# Microcontroller.net
KiCad netlist of a schematic drawn in Altium Designer
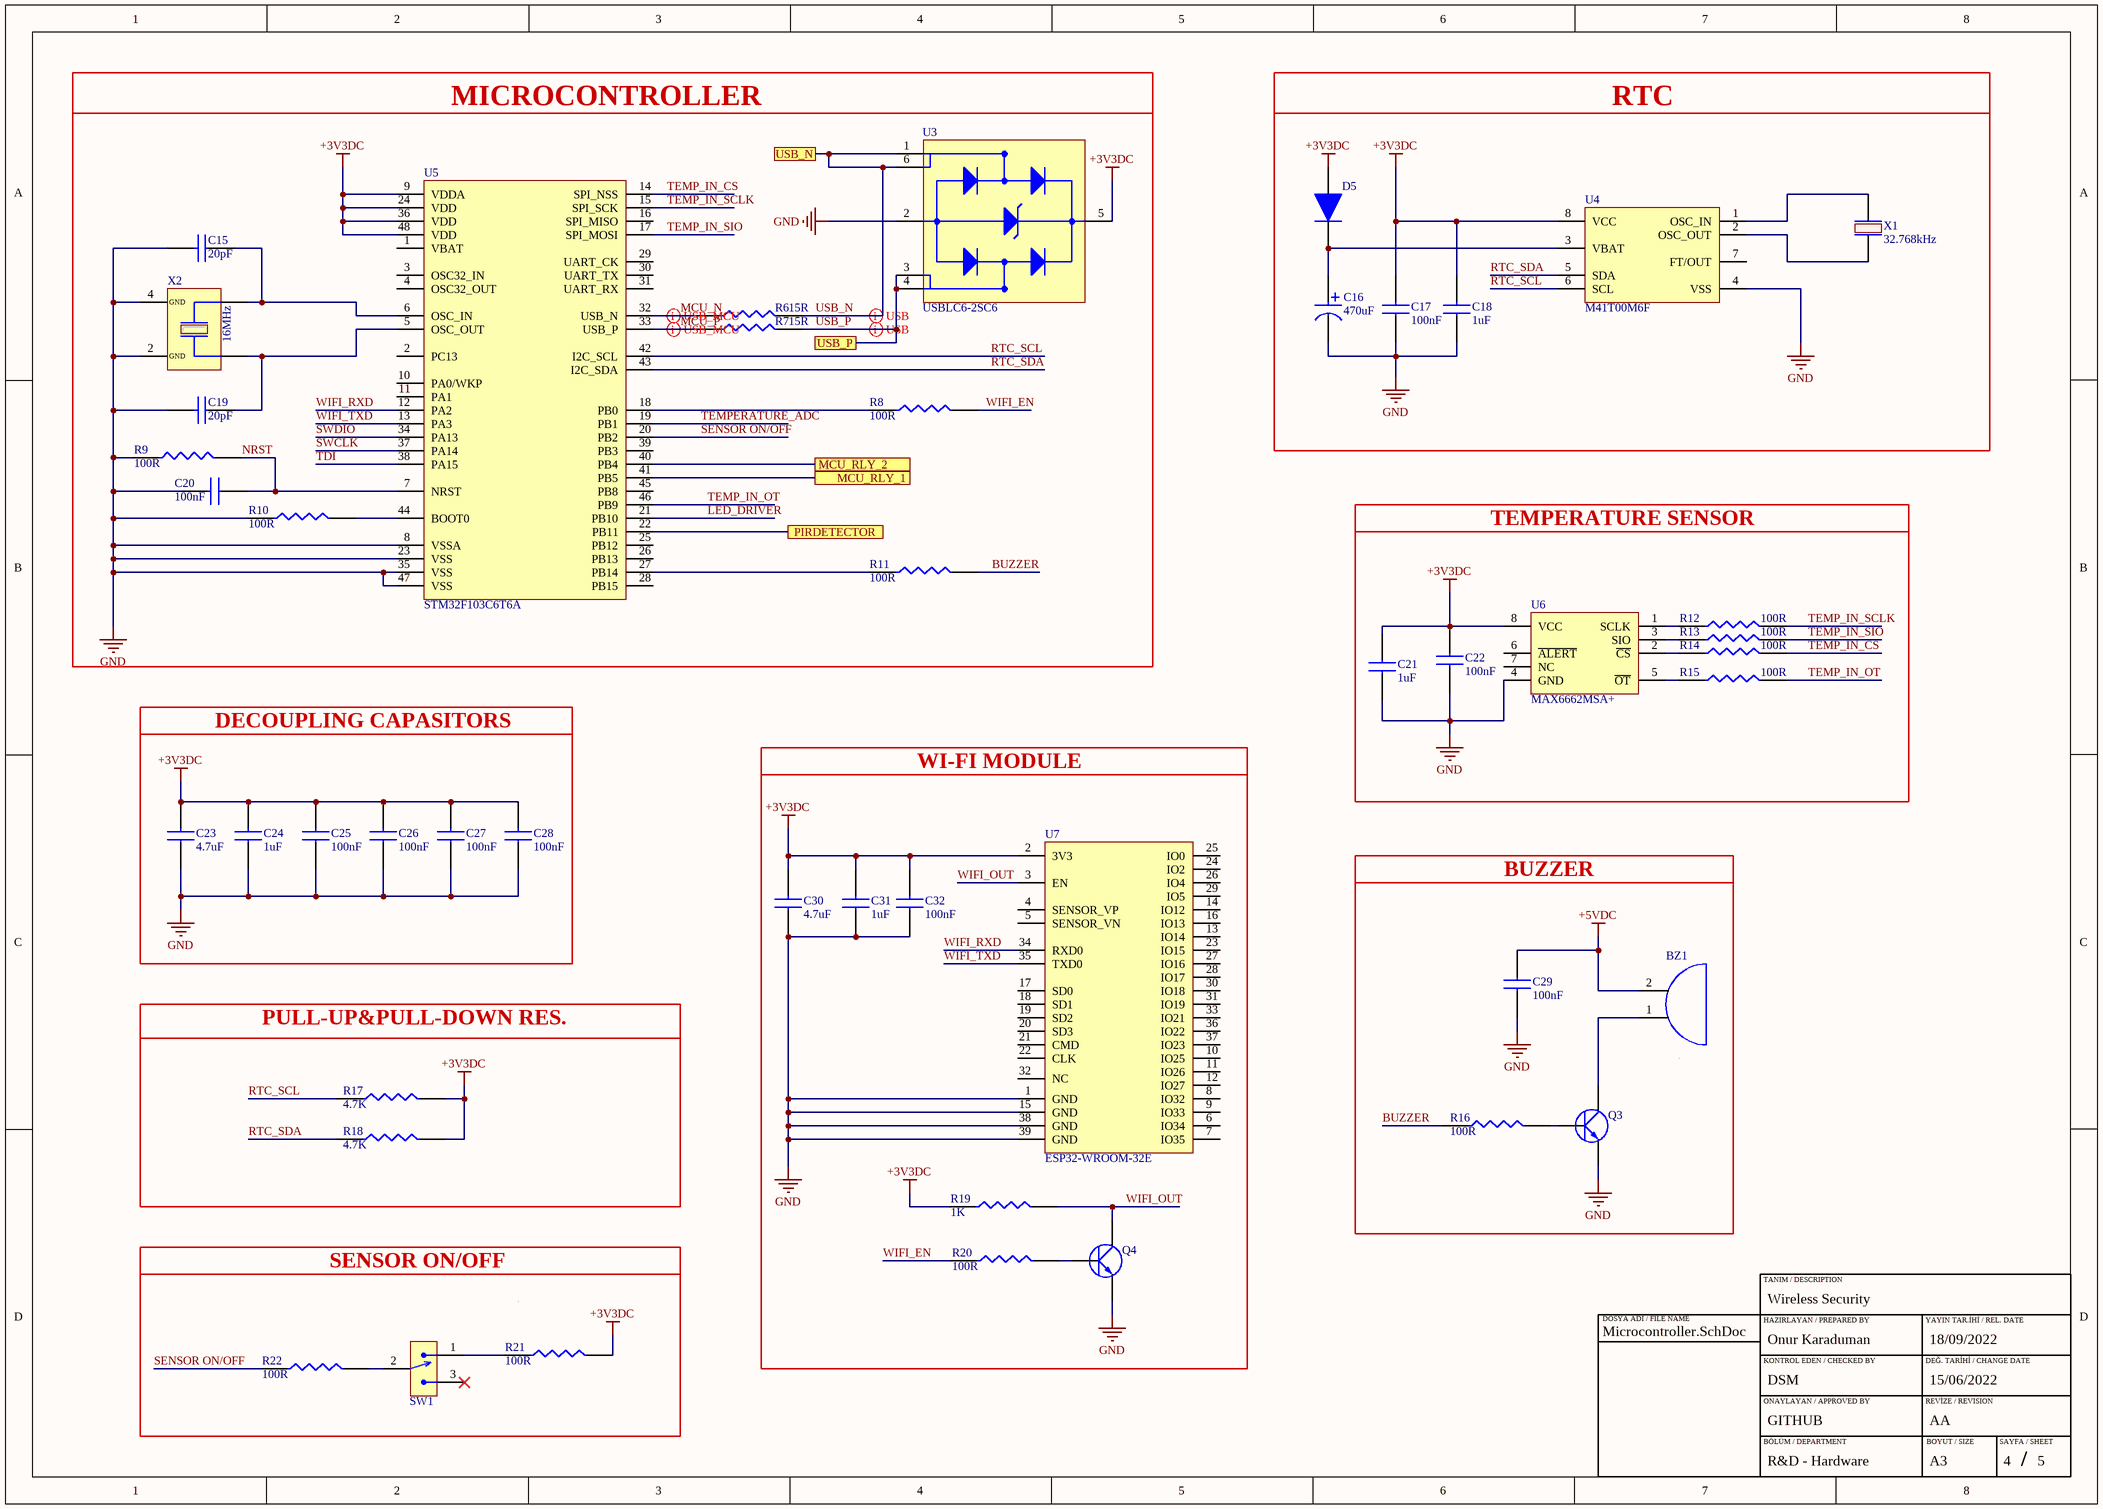
[diagram p0: Microcontroller.SchDoc]

(export (version "E")
  (design (tool "Eeschema 10.0.6"))
  (components
    (comp (ref "BZ1")
      (value "CMI-96051C-0580T")
      (footprint "CMI-9605IC-0580T")
      (description "Audio Buzzer Magnetic 3VDC 7VDC 30mA 5VDC 85dB 2600Hz to 2800Hz Through Hole Pin Box")
      (fields
        (field (name "MANUFACTURER") "CUI Devices")
        (field (name "MANUFACTURER PART NUMBER") "CMI-9605IC-0580T")
        (field (name "DESIGNED BY") "Onur Karaduman")
      )
      (libsource (lib "Ders1Lib") (part "CMI-96051C-0580T"))
    )
    (comp (ref "C15")
      (value "CL10C200JB8NNNC")
      (footprint "CAP_0603")
      (description "CAP CER 20pF %5 0603 SMD")
      (fields
        (field (name "MANUFACTURER") "Samsung")
        (field (name "TOLERANCE") "5%")
        (field (name "CAPACITANCE") "20pF")
        (field (name "DESIGNED BY") "BERK")
      )
      (libsource (lib "UDEMY_Library") (part "CAP CER 20pF 0603"))
    )
    (comp (ref "C16")
      (value "ESH477M050AH4AA")
      (footprint "ESH477M050AH4AA")
      (description "Cap, 470UF, 50V, Alu Elec, Radial")
      (fields
        (field (name "MANUFACTURER") "KEMET")
        (field (name "TOLERANCE") "20%")
        (field (name "CAPACITANCE") "470uF")
        (field (name "DESIGNED BY") "Onur Karaduman")
      )
      (libsource (lib "Ders1Lib") (part "ESH477M050AH4AA"))
    )
    (comp (ref "C17")
      (value "CL21B104KBCNNNC")
      (footprint "CAP_0805")
      (description "CAP CER 0.1UF 50V X7R 0805")
      (fields
        (field (name "MANUFACTURER") "Samsung")
        (field (name "TOLERANCE") "10%")
        (field (name "CAPACITANCE") "100nF")
        (field (name "DESIGNED BY") "Onur Karaduman")
      )
      (libsource (lib "Ders1Lib") (part "CAP CER 100nF 0805"))
    )
    (comp (ref "C18")
      (value "CL21B105KBFNNNE")
      (footprint "CAP_0805")
      (description "CAP CER 1UF 50V X7R 0805")
      (fields
        (field (name "MANUFACTURER") "Samsung")
        (field (name "TOLERANCE") "10%")
        (field (name "CAPACITANCE") "1uF")
        (field (name "DESIGNED BY") "Onur Karaduman")
      )
      (libsource (lib "Ders1Lib") (part "CAP CER 1uF 0805"))
    )
    (comp (ref "C19")
      (value "CL10C200JB8NNNC")
      (footprint "CAP_0603")
      (description "CAP CER 20pF %5 0603 SMD")
      (fields
        (field (name "MANUFACTURER") "Samsung")
        (field (name "TOLERANCE") "5%")
        (field (name "CAPACITANCE") "20pF")
        (field (name "DESIGNED BY") "BERK")
      )
      (libsource (lib "UDEMY_Library") (part "CAP CER 20pF 0603"))
    )
    (comp (ref "C20")
      (value "C0603C104K4RACTU")
      (footprint "CAP_0603")
      (description "Cap Cer 0.1uF 16V X7R 10% SMD 0603 125°C Paper T/R")
      (fields
        (field (name "MANUFACTURER") "KEMET")
        (field (name "TOLERANCE") "10%")
        (field (name "CAPACITANCE") "100nF")
        (field (name "DESIGNED BY") "Onur Karaduman")
      )
      (libsource (lib "Ders1Lib") (part "CAP CER 100nF 0603"))
    )
    (comp (ref "C21")
      (value "CL21B105KBFNNNE")
      (footprint "CAP_0805")
      (description "CAP CER 1UF 50V X7R 0805")
      (fields
        (field (name "MANUFACTURER") "Samsung")
        (field (name "TOLERANCE") "10%")
        (field (name "CAPACITANCE") "1uF")
        (field (name "DESIGNED BY") "Onur Karaduman")
      )
      (libsource (lib "Ders1Lib") (part "CAP CER 1uF 0805"))
    )
    (comp (ref "C22")
      (value "CL21B104KBCNNNC")
      (footprint "CAP_0805")
      (description "CAP CER 0.1UF 50V X7R 0805")
      (fields
        (field (name "MANUFACTURER") "Samsung")
        (field (name "TOLERANCE") "10%")
        (field (name "CAPACITANCE") "100nF")
        (field (name "DESIGNED BY") "Onur Karaduman")
      )
      (libsource (lib "Ders1Lib") (part "CAP CER 100nF 0805"))
    )
    (comp (ref "C23")
      (value "CL21A475KAQNNNE")
      (footprint "CAP_0805")
      (description "CAP CER 4.7UF 25V X5R 0805")
      (fields
        (field (name "MANUFACTURER") "Samsung")
        (field (name "TOLERANCE") "10%")
        (field (name "CAPACITANCE") "4.7uF")
        (field (name "DESIGNED BY") "Onur Karaduman")
      )
      (libsource (lib "Ders1Lib") (part "CAP CER 4.7uF 0805"))
    )
    (comp (ref "C24")
      (value "CL21B105KBFNNNE")
      (footprint "CAP_0805")
      (description "CAP CER 1UF 50V X7R 0805")
      (fields
        (field (name "MANUFACTURER") "Samsung")
        (field (name "TOLERANCE") "10%")
        (field (name "CAPACITANCE") "1uF")
        (field (name "DESIGNED BY") "Onur Karaduman")
      )
      (libsource (lib "Ders1Lib") (part "CAP CER 1uF 0805"))
    )
    (comp (ref "C25")
      (value "C0603C104K4RACTU")
      (footprint "CAP_0603")
      (description "Cap Cer 0.1uF 16V X7R 10% SMD 0603 125°C Paper T/R")
      (fields
        (field (name "MANUFACTURER") "KEMET")
        (field (name "TOLERANCE") "10%")
        (field (name "CAPACITANCE") "100nF")
        (field (name "DESIGNED BY") "Onur Karaduman")
      )
      (libsource (lib "Ders1Lib") (part "CAP CER 100nF 0603"))
    )
    (comp (ref "C26")
      (value "C0603C104K4RACTU")
      (footprint "CAP_0603")
      (description "Cap Cer 0.1uF 16V X7R 10% SMD 0603 125°C Paper T/R")
      (fields
        (field (name "MANUFACTURER") "KEMET")
        (field (name "TOLERANCE") "10%")
        (field (name "CAPACITANCE") "100nF")
        (field (name "DESIGNED BY") "Onur Karaduman")
      )
      (libsource (lib "Ders1Lib") (part "CAP CER 100nF 0603"))
    )
    (comp (ref "C27")
      (value "C0603C104K4RACTU")
      (footprint "CAP_0603")
      (description "Cap Cer 0.1uF 16V X7R 10% SMD 0603 125°C Paper T/R")
      (fields
        (field (name "MANUFACTURER") "KEMET")
        (field (name "TOLERANCE") "10%")
        (field (name "CAPACITANCE") "100nF")
        (field (name "DESIGNED BY") "Onur Karaduman")
      )
      (libsource (lib "Ders1Lib") (part "CAP CER 100nF 0603"))
    )
    (comp (ref "C28")
      (value "C0603C104K4RACTU")
      (footprint "CAP_0603")
      (description "Cap Cer 0.1uF 16V X7R 10% SMD 0603 125°C Paper T/R")
      (fields
        (field (name "MANUFACTURER") "KEMET")
        (field (name "TOLERANCE") "10%")
        (field (name "CAPACITANCE") "100nF")
        (field (name "DESIGNED BY") "Onur Karaduman")
      )
      (libsource (lib "Ders1Lib") (part "CAP CER 100nF 0603"))
    )
    (comp (ref "C29")
      (value "CL21B104KBCNNNC")
      (footprint "CAP_0805")
      (description "CAP CER 0.1UF 50V X7R 0805")
      (fields
        (field (name "MANUFACTURER") "Samsung")
        (field (name "TOLERANCE") "10%")
        (field (name "CAPACITANCE") "100nF")
        (field (name "DESIGNED BY") "Onur Karaduman")
      )
      (libsource (lib "Ders1Lib") (part "CAP CER 100nF 0805"))
    )
    (comp (ref "C30")
      (value "CL21A475KAQNNNE")
      (footprint "CAP_0805")
      (description "CAP CER 4.7UF 25V X5R 0805")
      (fields
        (field (name "MANUFACTURER") "Samsung")
        (field (name "TOLERANCE") "10%")
        (field (name "CAPACITANCE") "4.7uF")
        (field (name "DESIGNED BY") "Onur Karaduman")
      )
      (libsource (lib "Ders1Lib") (part "CAP CER 4.7uF 0805"))
    )
    (comp (ref "C31")
      (value "CL21B105KBFNNNE")
      (footprint "CAP_0805")
      (description "CAP CER 1UF 50V X7R 0805")
      (fields
        (field (name "MANUFACTURER") "Samsung")
        (field (name "TOLERANCE") "10%")
        (field (name "CAPACITANCE") "1uF")
        (field (name "DESIGNED BY") "Onur Karaduman")
      )
      (libsource (lib "Ders1Lib") (part "CAP CER 1uF 0805"))
    )
    (comp (ref "C32")
      (value "CL21B104KBCNNNC")
      (footprint "CAP_0805")
      (description "CAP CER 0.1UF 50V X7R 0805")
      (fields
        (field (name "MANUFACTURER") "Samsung")
        (field (name "TOLERANCE") "10%")
        (field (name "CAPACITANCE") "100nF")
        (field (name "DESIGNED BY") "Onur Karaduman")
      )
      (libsource (lib "Ders1Lib") (part "CAP CER 100nF 0805"))
    )
    (comp (ref "D5")
      (value "1N4148WS")
      (footprint "SOD32-F")
      (description "VR=75V IF=150mA Trr=4ns P=200mW")
      (fields
        (field (name "MANUFACTURER") "ON Semiconductor / Fairchild")
        (field (name "DESIGNED BY") "Onur Karaduman")
      )
      (libsource (lib "Ders1Lib") (part "1N4148WS"))
    )
    (comp (ref "Q3")
      (value "MMBT3904-7-F")
      (footprint "SOT23-F")
      (description "NPN Ic=200mA Vceo=40V hfe=100~300 fT=310MHz P=300mW SOT-23")
      (fields (field (name "MANUFACTURER") "Diodes Zetex") (field (name "DESIGNED BY") "Onur Karaduman"))
      (libsource (lib "Ders1Lib") (part "MMBT3904-7-F"))
    )
    (comp (ref "Q4")
      (value "MMBT3904-7-F")
      (footprint "SOT23-F")
      (description "NPN Ic=200mA Vceo=40V hfe=100~300 fT=310MHz P=300mW SOT-23")
      (fields (field (name "MANUFACTURER") "Diodes Zetex") (field (name "DESIGNED BY") "Onur Karaduman"))
      (libsource (lib "Ders1Lib") (part "MMBT3904-7-F"))
    )
    (comp (ref "R6")
      (value "RC0603JR-0715RL")
      (footprint "RES_0603")
      (description "Res Thick Film 0603 15 Ohm 5% 0.1W(1/10W) ±100ppm/C Pad SMD T/R")
      (fields
        (field (name "MANUFACTURER") "Yageo")
        (field (name "TOLERANCE") "5%")
        (field (name "RESISTANCE") "15R")
        (field (name "DESIGNED BY") "Onur Karaduman")
      )
      (libsource (lib "Ders1Lib") (part "RES 15 OHM 0603"))
    )
    (comp (ref "R7")
      (value "RC0603JR-0715RL")
      (footprint "RES_0603")
      (description "Res Thick Film 0603 15 Ohm 5% 0.1W(1/10W) ±100ppm/C Pad SMD T/R")
      (fields
        (field (name "MANUFACTURER") "Yageo")
        (field (name "TOLERANCE") "5%")
        (field (name "RESISTANCE") "15R")
        (field (name "DESIGNED BY") "Onur Karaduman")
      )
      (libsource (lib "Ders1Lib") (part "RES 15 OHM 0603"))
    )
    (comp (ref "R8")
      (value "RC0603JR-07100RL")
      (footprint "RES_0603")
      (description "Res Thick Film 0603 100 Ohm 5% 1/10W ±100ppm/°C Molded SMD SMD Paper T/R")
      (fields
        (field (name "MANUFACTURER") "Yageo")
        (field (name "TOLERANCE") "5%")
        (field (name "RESISTANCE") "100R")
        (field (name "DESIGNED BY") "Onur Karaduman")
      )
      (libsource (lib "Ders1Lib") (part "RES 100 OHM 0603"))
    )
    (comp (ref "R9")
      (value "RC0603JR-07100RL")
      (footprint "RES_0603")
      (description "Res Thick Film 0603 100 Ohm 5% 1/10W ±100ppm/°C Molded SMD SMD Paper T/R")
      (fields
        (field (name "MANUFACTURER") "Yageo")
        (field (name "TOLERANCE") "5%")
        (field (name "RESISTANCE") "100R")
        (field (name "DESIGNED BY") "Onur Karaduman")
      )
      (libsource (lib "Ders1Lib") (part "RES 100 OHM 0603"))
    )
    (comp (ref "R10")
      (value "RC0603JR-07100RL")
      (footprint "RES_0603")
      (description "Res Thick Film 0603 100 Ohm 5% 1/10W ±100ppm/°C Molded SMD SMD Paper T/R")
      (fields
        (field (name "MANUFACTURER") "Yageo")
        (field (name "TOLERANCE") "5%")
        (field (name "RESISTANCE") "100R")
        (field (name "DESIGNED BY") "Onur Karaduman")
      )
      (libsource (lib "Ders1Lib") (part "RES 100 OHM 0603"))
    )
    (comp (ref "R11")
      (value "RC0603JR-07100RL")
      (footprint "RES_0603")
      (description "Res Thick Film 0603 100 Ohm 5% 1/10W ±100ppm/°C Molded SMD SMD Paper T/R")
      (fields
        (field (name "MANUFACTURER") "Yageo")
        (field (name "TOLERANCE") "5%")
        (field (name "RESISTANCE") "100R")
        (field (name "DESIGNED BY") "Onur Karaduman")
      )
      (libsource (lib "Ders1Lib") (part "RES 100 OHM 0603"))
    )
    (comp (ref "R12")
      (value "RC0603JR-07100RL")
      (footprint "RES_0603")
      (description "Res Thick Film 0603 100 Ohm 5% 1/10W ±100ppm/°C Molded SMD SMD Paper T/R")
      (fields
        (field (name "MANUFACTURER") "Yageo")
        (field (name "TOLERANCE") "5%")
        (field (name "RESISTANCE") "100R")
        (field (name "DESIGNED BY") "Onur Karaduman")
      )
      (libsource (lib "Ders1Lib") (part "RES 100 OHM 0603"))
    )
    (comp (ref "R13")
      (value "RC0603JR-07100RL")
      (footprint "RES_0603")
      (description "Res Thick Film 0603 100 Ohm 5% 1/10W ±100ppm/°C Molded SMD SMD Paper T/R")
      (fields
        (field (name "MANUFACTURER") "Yageo")
        (field (name "TOLERANCE") "5%")
        (field (name "RESISTANCE") "100R")
        (field (name "DESIGNED BY") "Onur Karaduman")
      )
      (libsource (lib "Ders1Lib") (part "RES 100 OHM 0603"))
    )
    (comp (ref "R14")
      (value "RC0603JR-07100RL")
      (footprint "RES_0603")
      (description "Res Thick Film 0603 100 Ohm 5% 1/10W ±100ppm/°C Molded SMD SMD Paper T/R")
      (fields
        (field (name "MANUFACTURER") "Yageo")
        (field (name "TOLERANCE") "5%")
        (field (name "RESISTANCE") "100R")
        (field (name "DESIGNED BY") "Onur Karaduman")
      )
      (libsource (lib "Ders1Lib") (part "RES 100 OHM 0603"))
    )
    (comp (ref "R15")
      (value "RC0603JR-07100RL")
      (footprint "RES_0603")
      (description "Res Thick Film 0603 100 Ohm 5% 1/10W ±100ppm/°C Molded SMD SMD Paper T/R")
      (fields
        (field (name "MANUFACTURER") "Yageo")
        (field (name "TOLERANCE") "5%")
        (field (name "RESISTANCE") "100R")
        (field (name "DESIGNED BY") "Onur Karaduman")
      )
      (libsource (lib "Ders1Lib") (part "RES 100 OHM 0603"))
    )
    (comp (ref "R16")
      (value "RC0603JR-07100RL")
      (footprint "RES_0603")
      (description "Res Thick Film 0603 100 Ohm 5% 1/10W ±100ppm/°C Molded SMD SMD Paper T/R")
      (fields
        (field (name "MANUFACTURER") "Yageo")
        (field (name "TOLERANCE") "5%")
        (field (name "RESISTANCE") "100R")
        (field (name "DESIGNED BY") "Onur Karaduman")
      )
      (libsource (lib "Ders1Lib") (part "RES 100 OHM 0603"))
    )
    (comp (ref "R17")
      (value "RC0603JR-074K7L")
      (footprint "RES_0603")
      (description "Res General Purpose Thick Film 0603 4.7k Ohm 5% 1/10W ±100ppm/°C Molded Paper T/R")
      (fields
        (field (name "MANUFACTURER") "Yageo")
        (field (name "TOLERANCE") "5%")
        (field (name "RESISTANCE") "4.7K")
        (field (name "DESIGNED BY") "Onur Karaduman")
      )
      (libsource (lib "Ders1Lib") (part "RES 4K7 OHM 0603"))
    )
    (comp (ref "R18")
      (value "RC0603JR-074K7L")
      (footprint "RES_0603")
      (description "Res General Purpose Thick Film 0603 4.7k Ohm 5% 1/10W ±100ppm/°C Molded Paper T/R")
      (fields
        (field (name "MANUFACTURER") "Yageo")
        (field (name "TOLERANCE") "5%")
        (field (name "RESISTANCE") "4.7K")
        (field (name "DESIGNED BY") "Onur Karaduman")
      )
      (libsource (lib "Ders1Lib") (part "RES 4K7 OHM 0603"))
    )
    (comp (ref "R19")
      (value "RES 1K OHM 0603")
      (footprint "RES_0603")
      (description "Res Thick Film 0603 1K Ohm 1% 0.25W(1/4W) ±100ppm/°C Epoxy Resin Pad SMD Automotive T/R")
      (fields
        (field (name "MANUFACTURER") "Rohm")
        (field (name "MANUFACTURER PART NUMBER") "ESR03EZPF1001")
        (field (name "RESISTANCE") "1K")
        (field (name "DESIGNED BY") "Onur Karaduman")
      )
      (libsource (lib "Ders1Lib") (part "RES 1K OHM 0603"))
    )
    (comp (ref "R20")
      (value "RC0603JR-07100RL")
      (footprint "RES_0603")
      (description "Res Thick Film 0603 100 Ohm 5% 1/10W ±100ppm/°C Molded SMD SMD Paper T/R")
      (fields
        (field (name "MANUFACTURER") "Yageo")
        (field (name "TOLERANCE") "5%")
        (field (name "RESISTANCE") "100R")
        (field (name "DESIGNED BY") "Onur Karaduman")
      )
      (libsource (lib "Ders1Lib") (part "RES 100 OHM 0603"))
    )
    (comp (ref "R21")
      (value "RC0603JR-07100RL")
      (footprint "RES_0603")
      (description "Res Thick Film 0603 100 Ohm 5% 1/10W ±100ppm/°C Molded SMD SMD Paper T/R")
      (fields
        (field (name "MANUFACTURER") "Yageo")
        (field (name "TOLERANCE") "5%")
        (field (name "RESISTANCE") "100R")
        (field (name "DESIGNED BY") "Onur Karaduman")
      )
      (libsource (lib "Ders1Lib") (part "RES 100 OHM 0603"))
    )
    (comp (ref "R22")
      (value "RC0603JR-07100RL")
      (footprint "RES_0603")
      (description "Res Thick Film 0603 100 Ohm 5% 1/10W ±100ppm/°C Molded SMD SMD Paper T/R")
      (fields
        (field (name "MANUFACTURER") "Yageo")
        (field (name "TOLERANCE") "5%")
        (field (name "RESISTANCE") "100R")
        (field (name "DESIGNED BY") "Onur Karaduman")
      )
      (libsource (lib "Ders1Lib") (part "RES 100 OHM 0603"))
    )
    (comp (ref "SW1")
      (value "EG1215AA")
      (footprint "EG1215AA")
      (description "Slide Switch, SPDT, 0.025A, 24V, SMD")
      (fields
        (field (name "MANUFACTURER") "E-Switch")
        (field (name "TOLERANCE") "4.95%")
        (field (name "DESIGNED BY") "Onur Karaduman")
      )
      (libsource (lib "Ders1Lib") (part "EG1215AA"))
    )
    (comp (ref "U3")
      (value "USBLC6-2SC6")
      (footprint "SOT23-6L")
      (description "TVS DIODE 5.25VWM 17VC SOT23-6")
      (fields
        (field (name "MANUFACTURER") "STMicroelectronics")
        (field (name "DESIGNED BY") "Onur Karaduman")
      )
      (libsource (lib "Schlib1") (part "USB PROTECTİON"))
    )
    (comp (ref "U4")
      (value "M41T00M6F")
      (footprint "SOIC 8")
      (description "Real-time Clocks Clock/Calendar I2C, 2-Wire Serial 70uA @ 2.7V ~ 5.5V SOIC-8_150mil RoHS")
      (fields
        (field (name "MANUFACTURER") "STMicroelectronics")
        (field (name "MANUFACTURER PART NUMBER") "M41T00SM6F")
        (field (name "DESIGNED BY") "Onur Karaduman")
      )
      (libsource (lib "Ders1Lib") (part "M41T00M6F"))
    )
    (comp (ref "U5")
      (value "STM32F103C6T6A")
      (footprint "LQFP-48")
      (description "MCU 32-bit STM32F ARM Cortex M3 RISC 32KB Flash 2.5V/3.3V 48-Pin LQFP Tray")
      (fields
        (field (name "MANUFACTURER") "STMicroelectronics")
        (field (name "DESIGNED BY") "Onur Karaduman")
      )
      (libsource (lib "Ders1Lib") (part "STM32F103C6T6A"))
    )
    (comp (ref "U6")
      (value "MAX6662MSA+")
      (footprint "SOIC 8")
      (description "Temp Sensor Digital Serial (3-Wire, SPI) 8-Pin SOIC N Tube")
      (fields (field (name "MANUFACTURER") "Maxim") (field (name "DESIGNED BY") "Onur Karaduman"))
      (libsource (lib "Ders1Lib") (part "MAX6662MSA+"))
    )
    (comp (ref "U7")
      (value "ESP32-WROOM-32E")
      (footprint "ESP32-32E")
      (description "Rx Txrx Mod Wifi Trace Ant SMD")
      (fields
        (field (name "MANUFACTURER") "Espressif Systems")
        (field (name "MANUFACTURER PART NUMBER") "ESP32-WROOM-32E(M113EH3200PH3Q0)")
        (field (name "DESIGNED BY") "Onur Karaduman")
      )
      (libsource (lib "Ders1Lib") (part "ESP32-WROOM-32"))
    )
    (comp (ref "X1")
      (value "ABS05-32.768KHZ-T")
      (footprint "ABS05-32.768KHZ-T")
      (description "ABRACON - ABS05-32.768KHZ-T - Crystal, 32.768 kHz, SMD, 1.6mm x 1mm, 12.5 pF, 20 ppm, ABS05 Series")
      (fields
        (field (name "MANUFACTURER") "Abracon")
        (field (name "TOLERANCE") "20ppm")
        (field (name "FREQUENCY") "32.768kHz")
        (field (name "DESIGNED BY") "Onur Karaduman")
      )
      (libsource (lib "Ders1Lib") (part "CRYSTAL 327680 KHZ"))
    )
    (comp (ref "X2")
      (value "CRYSTAL 16.0000MHZ 20PF SMD")
      (footprint "ECS-160-20-30B")
      (description "Crystal 16MHz ±30ppm (Tol) ±50ppm (Stability) 20pF FUND 50Ohm 4-Pin Mini-SMD T/R")
      (fields
        (field (name "MANUFACTURER") "ECS International")
        (field (name "MANUFACTURER PART NUMBER") "ECS-160-20-30B-TR")
        (field (name "FREQUENCY") "16MHz")
        (field (name "DESIGNED BY") "Onur Karaduman")
      )
      (libsource (lib "Ders1Lib") (part "CRYSTAL 160000 MHZ"))
    )
  )
  (nets
    (net (code "1") (name "+3V3DC") (class "Default")
      (node (ref "C17") (pin "2") (pintype "passive"))
      (node (ref "C18") (pin "2") (pintype "passive"))
      (node (ref "C21") (pin "2") (pintype "passive"))
      (node (ref "C22") (pin "2") (pintype "passive"))
      (node (ref "C23") (pin "2") (pintype "passive"))
      (node (ref "C24") (pin "2") (pintype "passive"))
      (node (ref "C25") (pin "2") (pintype "passive"))
      (node (ref "C26") (pin "2") (pintype "passive"))
      (node (ref "C27") (pin "2") (pintype "passive"))
      (node (ref "C28") (pin "2") (pintype "passive"))
      (node (ref "C30") (pin "2") (pintype "passive"))
      (node (ref "C31") (pin "2") (pintype "passive"))
      (node (ref "C32") (pin "2") (pintype "passive"))
      (node (ref "D5") (pin "2") (pinfunction "2_2") (pintype "passive"))
      (node (ref "R17") (pin "2") (pintype "passive"))
      (node (ref "R18") (pin "2") (pintype "passive"))
      (node (ref "R19") (pin "1") (pintype "passive"))
      (node (ref "R21") (pin "2") (pintype "passive"))
      (node (ref "U3") (pin "5") (pinfunction "VBUS_5") (pintype "passive"))
      (node (ref "U4") (pin "8") (pinfunction "VCC_8") (pintype "passive"))
      (node (ref "U5") (pin "24") (pinfunction "VDD_24") (pintype "passive"))
      (node (ref "U5") (pin "36") (pinfunction "VDD_36") (pintype "passive"))
      (node (ref "U5") (pin "48") (pinfunction "VDD_48") (pintype "passive"))
      (node (ref "U5") (pin "9") (pinfunction "VDDA_9") (pintype "passive"))
      (node (ref "U6") (pin "8") (pinfunction "VCC_8") (pintype "passive"))
      (node (ref "U7") (pin "2") (pinfunction "3V3_2") (pintype "passive"))
    )
    (net (code "2") (name "+5VDC") (class "Default")
      (node (ref "BZ1") (pin "2") (pintype "passive"))
      (node (ref "C29") (pin "2") (pintype "passive"))
    )
    (net (code "3") (name "/BUZZER") (class "Default")
      (node (ref "R11") (pin "2") (pintype "passive"))
      (node (ref "R16") (pin "1") (pintype "passive"))
    )
    (net (code "4") (name "/LED_DRIVER") (class "Default")
      (node (ref "U5") (pin "21") (pinfunction "PB10_21") (pintype "passive"))
    )
    (net (code "5") (name "/MCU_N") (class "Default")
      (node (ref "R6") (pin "1") (pintype "passive"))
      (node (ref "U5") (pin "32") (pinfunction "USB_N_32") (pintype "passive"))
    )
    (net (code "6") (name "/MCU_P") (class "Default")
      (node (ref "R7") (pin "1") (pintype "passive"))
      (node (ref "U5") (pin "33") (pinfunction "USB_P_33") (pintype "passive"))
    )
    (net (code "7") (name "/MCU_RLY_1") (class "Default")
      (node (ref "U5") (pin "41") (pinfunction "PB5_41") (pintype "passive"))
    )
    (net (code "8") (name "/MCU_RLY_2") (class "Default")
      (node (ref "U5") (pin "40") (pinfunction "PB4_40") (pintype "passive"))
    )
    (net (code "9") (name "/NRST") (class "Default")
      (node (ref "C20") (pin "1") (pintype "passive"))
      (node (ref "R9") (pin "2") (pintype "passive"))
      (node (ref "U5") (pin "7") (pinfunction "NRST_7") (pintype "passive"))
    )
    (net (code "10") (name "/PIRDETECTOR") (class "Default")
      (node (ref "U5") (pin "22") (pinfunction "PB11_22") (pintype "passive"))
    )
    (net (code "11") (name "/RTC_SCL") (class "Default")
      (node (ref "R17") (pin "1") (pintype "passive"))
      (node (ref "U4") (pin "6") (pinfunction "SCL_6") (pintype "passive"))
      (node (ref "U5") (pin "42") (pinfunction "I2C_SCL_42") (pintype "passive"))
    )
    (net (code "12") (name "/RTC_SDA") (class "Default")
      (node (ref "R18") (pin "1") (pintype "passive"))
      (node (ref "U4") (pin "5") (pinfunction "SDA_5") (pintype "passive"))
      (node (ref "U5") (pin "43") (pinfunction "I2C_SDA_43") (pintype "passive"))
    )
    (net (code "13") (name "/SENSOR ON{slash}OFF") (class "Default")
      (node (ref "R22") (pin "1") (pintype "passive"))
      (node (ref "U5") (pin "20") (pinfunction "PB2_20") (pintype "passive"))
    )
    (net (code "14") (name "/SWCLK") (class "Default")
      (node (ref "U5") (pin "37") (pinfunction "PA14_37") (pintype "passive"))
    )
    (net (code "15") (name "/SWDIO") (class "Default")
      (node (ref "U5") (pin "34") (pinfunction "PA13_34") (pintype "passive"))
    )
    (net (code "16") (name "/TDI") (class "Default")
      (node (ref "U5") (pin "38") (pinfunction "PA15_38") (pintype "passive"))
    )
    (net (code "17") (name "/TEMPERATURE_ADC") (class "Default")
      (node (ref "U5") (pin "19") (pinfunction "PB1_19") (pintype "passive"))
    )
    (net (code "18") (name "/TEMP_IN_CS") (class "Default")
      (node (ref "R14") (pin "2") (pintype "passive"))
      (node (ref "U5") (pin "14") (pinfunction "SPI_NSS_14") (pintype "passive"))
    )
    (net (code "19") (name "/TEMP_IN_OT") (class "Default")
      (node (ref "R15") (pin "2") (pintype "passive"))
      (node (ref "U5") (pin "46") (pinfunction "PB9_46") (pintype "passive"))
    )
    (net (code "20") (name "/TEMP_IN_SCLK") (class "Default")
      (node (ref "R12") (pin "2") (pintype "passive"))
      (node (ref "U5") (pin "15") (pinfunction "SPI_SCK_15") (pintype "passive"))
    )
    (net (code "21") (name "/TEMP_IN_SIO") (class "Default")
      (node (ref "R13") (pin "2") (pintype "passive"))
      (node (ref "U5") (pin "17") (pinfunction "SPI_MOSI_17") (pintype "passive"))
    )
    (net (code "22") (name "/USB_N") (class "Default")
      (node (ref "R6") (pin "2") (pintype "passive"))
      (node (ref "U3") (pin "1") (pinfunction "I/O1_IN_1") (pintype "passive"))
      (node (ref "U3") (pin "6") (pinfunction "I/O1_OUT_6") (pintype "passive"))
    )
    (net (code "23") (name "/USB_P") (class "Default")
      (node (ref "R7") (pin "2") (pintype "passive"))
      (node (ref "U3") (pin "3") (pinfunction "I/O2_IN_3") (pintype "passive"))
      (node (ref "U3") (pin "4") (pinfunction "I/O2_OUT_4") (pintype "passive"))
    )
    (net (code "24") (name "/WIFI_EN") (class "Default")
      (node (ref "R20") (pin "1") (pintype "passive"))
      (node (ref "R8") (pin "2") (pintype "passive"))
    )
    (net (code "25") (name "/WIFI_OUT") (class "Default")
      (node (ref "Q4") (pin "3") (pinfunction "_3_3") (pintype "passive"))
      (node (ref "R19") (pin "2") (pintype "passive"))
      (node (ref "U7") (pin "3") (pinfunction "EN_3") (pintype "passive"))
    )
    (net (code "26") (name "/WIFI_RXD") (class "Default")
      (node (ref "U5") (pin "12") (pinfunction "PA2_12") (pintype "passive"))
      (node (ref "U7") (pin "34") (pinfunction "RXD0_34") (pintype "passive"))
    )
    (net (code "27") (name "/WIFI_TXD") (class "Default")
      (node (ref "U5") (pin "13") (pinfunction "PA3_13") (pintype "passive"))
      (node (ref "U7") (pin "35") (pinfunction "TXD0_35") (pintype "passive"))
    )
    (net (code "28") (name "GND") (class "Default")
      (node (ref "C15") (pin "2") (pinfunction "2_2") (pintype "passive"))
      (node (ref "C16") (pin "2") (pintype "passive"))
      (node (ref "C17") (pin "1") (pintype "passive"))
      (node (ref "C18") (pin "1") (pintype "passive"))
      (node (ref "C19") (pin "2") (pinfunction "2_2") (pintype "passive"))
      (node (ref "C20") (pin "2") (pintype "passive"))
      (node (ref "C21") (pin "1") (pintype "passive"))
      (node (ref "C22") (pin "1") (pintype "passive"))
      (node (ref "C23") (pin "1") (pintype "passive"))
      (node (ref "C24") (pin "1") (pintype "passive"))
      (node (ref "C25") (pin "1") (pintype "passive"))
      (node (ref "C26") (pin "1") (pintype "passive"))
      (node (ref "C27") (pin "1") (pintype "passive"))
      (node (ref "C28") (pin "1") (pintype "passive"))
      (node (ref "C29") (pin "1") (pintype "passive"))
      (node (ref "C30") (pin "1") (pintype "passive"))
      (node (ref "C31") (pin "1") (pintype "passive"))
      (node (ref "C32") (pin "1") (pintype "passive"))
      (node (ref "Q3") (pin "2") (pinfunction "2_2") (pintype "passive"))
      (node (ref "Q4") (pin "2") (pinfunction "2_2") (pintype "passive"))
      (node (ref "R10") (pin "1") (pintype "passive"))
      (node (ref "R9") (pin "1") (pintype "passive"))
      (node (ref "U3") (pin "2") (pinfunction "GND_2") (pintype "passive"))
      (node (ref "U4") (pin "4") (pinfunction "VSS_4") (pintype "passive"))
      (node (ref "U5") (pin "23") (pinfunction "VSS_23") (pintype "passive"))
      (node (ref "U5") (pin "35") (pinfunction "VSS_35") (pintype "passive"))
      (node (ref "U5") (pin "47") (pinfunction "VSS_47") (pintype "passive"))
      (node (ref "U5") (pin "8") (pinfunction "VSSA_8") (pintype "passive"))
      (node (ref "U6") (pin "4") (pinfunction "GND_4") (pintype "passive"))
      (node (ref "U7") (pin "1") (pinfunction "GND_1") (pintype "passive"))
      (node (ref "U7") (pin "15") (pinfunction "GND_15") (pintype "passive"))
      (node (ref "U7") (pin "38") (pinfunction "GND_38") (pintype "passive"))
      (node (ref "U7") (pin "39") (pinfunction "GND_39") (pintype "passive"))
      (node (ref "X2") (pin "2") (pinfunction "GND_2") (pintype "passive"))
      (node (ref "X2") (pin "4") (pinfunction "GND_4") (pintype "passive"))
    )
    (net (code "29") (name "Net-(Q3-Pad1)") (class "Default")
      (node (ref "Q3") (pin "1") (pinfunction "1_1") (pintype "passive"))
      (node (ref "R16") (pin "2") (pintype "passive"))
    )
    (net (code "30") (name "Net-(Q3-_3)") (class "Default")
      (node (ref "BZ1") (pin "1") (pintype "passive"))
      (node (ref "Q3") (pin "3") (pinfunction "_3_3") (pintype "passive"))
    )
    (net (code "31") (name "Net-(Q4-Pad1)") (class "Default")
      (node (ref "Q4") (pin "1") (pinfunction "1_1") (pintype "passive"))
      (node (ref "R20") (pin "2") (pintype "passive"))
    )
    (net (code "32") (name "Net-(R21-Pad1)") (class "Default")
      (node (ref "R21") (pin "1") (pintype "passive"))
      (node (ref "SW1") (pin "1") (pintype "passive"))
    )
    (net (code "33") (name "Net-(R22-Pad2)") (class "Default")
      (node (ref "R22") (pin "2") (pintype "passive"))
      (node (ref "SW1") (pin "2") (pintype "passive"))
    )
    (net (code "34") (name "Net-(U4-OSC_IN)") (class "Default")
      (node (ref "U4") (pin "1") (pinfunction "OSC_IN_1") (pintype "passive"))
      (node (ref "X1") (pin "2") (pinfunction "8_2") (pintype "passive"))
    )
    (net (code "35") (name "Net-(U4-OSC_OUT)") (class "Default")
      (node (ref "U4") (pin "2") (pinfunction "OSC_OUT_2") (pintype "passive"))
      (node (ref "X1") (pin "1") (pinfunction "7_1") (pintype "passive"))
    )
    (net (code "36") (name "Net-(U4-VBAT)") (class "Default")
      (node (ref "C16") (pin "1") (pintype "passive"))
      (node (ref "D5") (pin "1") (pintype "passive"))
      (node (ref "U4") (pin "3") (pinfunction "VBAT_3") (pintype "passive"))
    )
    (net (code "37") (name "Net-(U5-BOOT0)") (class "Default")
      (node (ref "R10") (pin "2") (pintype "passive"))
      (node (ref "U5") (pin "44") (pinfunction "BOOT0_44") (pintype "passive"))
    )
    (net (code "38") (name "Net-(U5-OSC_IN)") (class "Default")
      (node (ref "C15") (pin "1") (pinfunction "1_1") (pintype "passive"))
      (node (ref "U5") (pin "6") (pinfunction "OSC_IN_6") (pintype "passive"))
      (node (ref "X2") (pin "1") (pintype "passive"))
    )
    (net (code "39") (name "Net-(U5-OSC_OUT)") (class "Default")
      (node (ref "C19") (pin "1") (pinfunction "1_1") (pintype "passive"))
      (node (ref "U5") (pin "5") (pinfunction "OSC_OUT_5") (pintype "passive"))
      (node (ref "X2") (pin "3") (pintype "passive"))
    )
    (net (code "40") (name "Net-(U5-PB0)") (class "Default")
      (node (ref "R8") (pin "1") (pintype "passive"))
      (node (ref "U5") (pin "18") (pinfunction "PB0_18") (pintype "passive"))
    )
    (net (code "41") (name "Net-(U5-PB14)") (class "Default")
      (node (ref "R11") (pin "1") (pintype "passive"))
      (node (ref "U5") (pin "27") (pinfunction "PB14_27") (pintype "passive"))
    )
    (net (code "42") (name "Net-(U6-SCLK)") (class "Default")
      (node (ref "R12") (pin "1") (pintype "passive"))
      (node (ref "U6") (pin "1") (pinfunction "SCLK_1") (pintype "passive"))
    )
    (net (code "43") (name "Net-(U6-SIO)") (class "Default")
      (node (ref "R13") (pin "1") (pintype "passive"))
      (node (ref "U6") (pin "3") (pinfunction "SIO_3") (pintype "passive"))
    )
    (net (code "44") (name "Net-(U6-~{CS})") (class "Default")
      (node (ref "R14") (pin "1") (pintype "passive"))
      (node (ref "U6") (pin "2") (pinfunction "~{CS}_2") (pintype "passive"))
    )
    (net (code "45") (name "Net-(U6-~{OT})") (class "Default")
      (node (ref "R15") (pin "1") (pintype "passive"))
      (node (ref "U6") (pin "5") (pinfunction "~{OT}_5") (pintype "passive"))
    )
    (net (code "46") (name "unconnected-(SW1-Pad3)") (class "Default")
      (node (ref "SW1") (pin "3") (pintype "passive+no_connect"))
    )
    (net (code "47") (name "unconnected-(U4-FT{slash}OUT-Pad7)") (class "Default")
      (node (ref "U4") (pin "7") (pinfunction "FT/OUT_7") (pintype "passive"))
    )
    (net (code "48") (name "unconnected-(U5-OSC32_IN-Pad3)") (class "Default")
      (node (ref "U5") (pin "3") (pinfunction "OSC32_IN_3") (pintype "passive"))
    )
    (net (code "49") (name "unconnected-(U5-OSC32_OUT-Pad4)") (class "Default")
      (node (ref "U5") (pin "4") (pinfunction "OSC32_OUT_4") (pintype "passive"))
    )
    (net (code "50") (name "unconnected-(U5-PA0{slash}WKP-Pad10)") (class "Default")
      (node (ref "U5") (pin "10") (pinfunction "PA0/WKP_10") (pintype "passive"))
    )
    (net (code "51") (name "unconnected-(U5-PA1-Pad11)") (class "Default")
      (node (ref "U5") (pin "11") (pinfunction "PA1_11") (pintype "passive"))
    )
    (net (code "52") (name "unconnected-(U5-PB3-Pad39)") (class "Default")
      (node (ref "U5") (pin "39") (pinfunction "PB3_39") (pintype "passive"))
    )
    (net (code "53") (name "unconnected-(U5-PB8-Pad45)") (class "Default")
      (node (ref "U5") (pin "45") (pinfunction "PB8_45") (pintype "passive"))
    )
    (net (code "54") (name "unconnected-(U5-PB12-Pad25)") (class "Default")
      (node (ref "U5") (pin "25") (pinfunction "PB12_25") (pintype "passive"))
    )
    (net (code "55") (name "unconnected-(U5-PB13-Pad26)") (class "Default")
      (node (ref "U5") (pin "26") (pinfunction "PB13_26") (pintype "passive"))
    )
    (net (code "56") (name "unconnected-(U5-PB15-Pad28)") (class "Default")
      (node (ref "U5") (pin "28") (pinfunction "PB15_28") (pintype "passive"))
    )
    (net (code "57") (name "unconnected-(U5-PC13-Pad2)") (class "Default")
      (node (ref "U5") (pin "2") (pinfunction "PC13_2") (pintype "passive"))
    )
    (net (code "58") (name "unconnected-(U5-SPI_MISO-Pad16)") (class "Default")
      (node (ref "U5") (pin "16") (pinfunction "SPI_MISO_16") (pintype "passive"))
    )
    (net (code "59") (name "unconnected-(U5-UART_CK-Pad29)") (class "Default")
      (node (ref "U5") (pin "29") (pinfunction "UART_CK_29") (pintype "passive"))
    )
    (net (code "60") (name "unconnected-(U5-UART_RX-Pad31)") (class "Default")
      (node (ref "U5") (pin "31") (pinfunction "UART_RX_31") (pintype "passive"))
    )
    (net (code "61") (name "unconnected-(U5-UART_TX-Pad30)") (class "Default")
      (node (ref "U5") (pin "30") (pinfunction "UART_TX_30") (pintype "passive"))
    )
    (net (code "62") (name "unconnected-(U5-VBAT-Pad1)") (class "Default")
      (node (ref "U5") (pin "1") (pinfunction "VBAT_1") (pintype "passive"))
    )
    (net (code "63") (name "unconnected-(U6-NC-Pad7)") (class "Default")
      (node (ref "U6") (pin "7") (pinfunction "NC_7") (pintype "passive"))
    )
    (net (code "64") (name "unconnected-(U6-~{ALERT}-Pad6)") (class "Default")
      (node (ref "U6") (pin "6") (pinfunction "~{ALERT}_6") (pintype "passive"))
    )
    (net (code "65") (name "unconnected-(U7-CLK-Pad22)") (class "Default")
      (node (ref "U7") (pin "22") (pinfunction "CLK_22") (pintype "passive"))
    )
    (net (code "66") (name "unconnected-(U7-CMD-Pad21)") (class "Default")
      (node (ref "U7") (pin "21") (pinfunction "CMD_21") (pintype "passive"))
    )
    (net (code "67") (name "unconnected-(U7-IO0-Pad25)") (class "Default")
      (node (ref "U7") (pin "25") (pinfunction "IO0_25") (pintype "passive"))
    )
    (net (code "68") (name "unconnected-(U7-IO2-Pad24)") (class "Default")
      (node (ref "U7") (pin "24") (pinfunction "IO2_24") (pintype "passive"))
    )
    (net (code "69") (name "unconnected-(U7-IO4-Pad26)") (class "Default")
      (node (ref "U7") (pin "26") (pinfunction "IO4_26") (pintype "passive"))
    )
    (net (code "70") (name "unconnected-(U7-IO5-Pad29)") (class "Default")
      (node (ref "U7") (pin "29") (pinfunction "IO5_29") (pintype "passive"))
    )
    (net (code "71") (name "unconnected-(U7-IO12-Pad14)") (class "Default")
      (node (ref "U7") (pin "14") (pinfunction "IO12_14") (pintype "passive"))
    )
    (net (code "72") (name "unconnected-(U7-IO13-Pad16)") (class "Default")
      (node (ref "U7") (pin "16") (pinfunction "IO13_16") (pintype "passive"))
    )
    (net (code "73") (name "unconnected-(U7-IO14-Pad13)") (class "Default")
      (node (ref "U7") (pin "13") (pinfunction "IO14_13") (pintype "passive"))
    )
    (net (code "74") (name "unconnected-(U7-IO15-Pad23)") (class "Default")
      (node (ref "U7") (pin "23") (pinfunction "IO15_23") (pintype "passive"))
    )
    (net (code "75") (name "unconnected-(U7-IO16-Pad27)") (class "Default")
      (node (ref "U7") (pin "27") (pinfunction "IO16_27") (pintype "passive"))
    )
    (net (code "76") (name "unconnected-(U7-IO17-Pad28)") (class "Default")
      (node (ref "U7") (pin "28") (pinfunction "IO17_28") (pintype "passive"))
    )
    (net (code "77") (name "unconnected-(U7-IO18-Pad30)") (class "Default")
      (node (ref "U7") (pin "30") (pinfunction "IO18_30") (pintype "passive"))
    )
    (net (code "78") (name "unconnected-(U7-IO19-Pad31)") (class "Default")
      (node (ref "U7") (pin "31") (pinfunction "IO19_31") (pintype "passive"))
    )
    (net (code "79") (name "unconnected-(U7-IO21-Pad33)") (class "Default")
      (node (ref "U7") (pin "33") (pinfunction "IO21_33") (pintype "passive"))
    )
    (net (code "80") (name "unconnected-(U7-IO22-Pad36)") (class "Default")
      (node (ref "U7") (pin "36") (pinfunction "IO22_36") (pintype "passive"))
    )
    (net (code "81") (name "unconnected-(U7-IO23-Pad37)") (class "Default")
      (node (ref "U7") (pin "37") (pinfunction "IO23_37") (pintype "passive"))
    )
    (net (code "82") (name "unconnected-(U7-IO25-Pad10)") (class "Default")
      (node (ref "U7") (pin "10") (pinfunction "IO25_10") (pintype "passive"))
    )
    (net (code "83") (name "unconnected-(U7-IO26-Pad11)") (class "Default")
      (node (ref "U7") (pin "11") (pinfunction "IO26_11") (pintype "passive"))
    )
    (net (code "84") (name "unconnected-(U7-IO27-Pad12)") (class "Default")
      (node (ref "U7") (pin "12") (pinfunction "IO27_12") (pintype "passive"))
    )
    (net (code "85") (name "unconnected-(U7-IO32-Pad8)") (class "Default")
      (node (ref "U7") (pin "8") (pinfunction "IO32_8") (pintype "passive"))
    )
    (net (code "86") (name "unconnected-(U7-IO33-Pad9)") (class "Default")
      (node (ref "U7") (pin "9") (pinfunction "IO33_9") (pintype "passive"))
    )
    (net (code "87") (name "unconnected-(U7-IO34-Pad6)") (class "Default")
      (node (ref "U7") (pin "6") (pinfunction "IO34_6") (pintype "passive"))
    )
    (net (code "88") (name "unconnected-(U7-IO35-Pad7)") (class "Default")
      (node (ref "U7") (pin "7") (pinfunction "IO35_7") (pintype "passive"))
    )
    (net (code "89") (name "unconnected-(U7-NC-Pad32)") (class "Default")
      (node (ref "U7") (pin "32") (pinfunction "NC_32") (pintype "passive"))
    )
    (net (code "90") (name "unconnected-(U7-SD0-Pad17)") (class "Default")
      (node (ref "U7") (pin "17") (pinfunction "SD0_17") (pintype "passive"))
    )
    (net (code "91") (name "unconnected-(U7-SD1-Pad18)") (class "Default")
      (node (ref "U7") (pin "18") (pinfunction "SD1_18") (pintype "passive"))
    )
    (net (code "92") (name "unconnected-(U7-SD2-Pad19)") (class "Default")
      (node (ref "U7") (pin "19") (pinfunction "SD2_19") (pintype "passive"))
    )
    (net (code "93") (name "unconnected-(U7-SD3-Pad20)") (class "Default")
      (node (ref "U7") (pin "20") (pinfunction "SD3_20") (pintype "passive"))
    )
    (net (code "94") (name "unconnected-(U7-SENSOR_VN-Pad5)") (class "Default")
      (node (ref "U7") (pin "5") (pinfunction "SENSOR_VN_5") (pintype "passive"))
    )
    (net (code "95") (name "unconnected-(U7-SENSOR_VP-Pad4)") (class "Default")
      (node (ref "U7") (pin "4") (pinfunction "SENSOR_VP_4") (pintype "passive"))
    )
  )
)
